# tactswitch.net
KiCad netlist of a schematic drawn in EAGLE
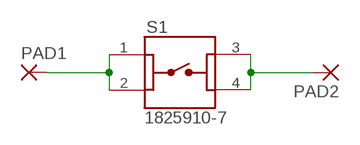
[diagram p0: schematic, sheet 1]

(export (version "E")
  (design (tool "Eeschema 10.0.6"))
  (components
    (comp (ref "PAD1")
      (value "2,15/1,0")
      (footprint "eagle-import:2,15_1,0")
      (libsource (lib "eagle-import") (part "2,15/1,0"))
    )
    (comp (ref "PAD2")
      (value "2,15/1,0")
      (footprint "eagle-import:2,15_1,0")
      (libsource (lib "eagle-import") (part "2,15/1,0"))
    )
    (comp (ref "S1")
      (value "1825910-7")
      (footprint "eagle-import:SW_1825910-7")
      (fields (field (name "DIGI-KEY_PART_NUMBER") "450-1804-ND") (field (name "MF") "TE Connectivity"))
      (libsource (lib "eagle-import") (part "1825910-7"))
    )
  )
  (nets
    (net (code "1") (name "Net-(PAD1-P)") (class "Default")
      (node (ref "PAD1") (pin "1") (pinfunction "P_1") (pintype "passive"))
      (node (ref "S1") (pin "1") (pinfunction "1_1") (pintype "passive"))
      (node (ref "S1") (pin "2") (pinfunction "2_2") (pintype "passive"))
    )
    (net (code "2") (name "Net-(PAD2-P)") (class "Default")
      (node (ref "PAD2") (pin "1") (pinfunction "P_1") (pintype "passive"))
      (node (ref "S1") (pin "3") (pinfunction "3_3") (pintype "passive"))
      (node (ref "S1") (pin "4") (pinfunction "4_4") (pintype "passive"))
    )
  )
)
